# MySensors_org-BaseSensorWithPIR.net
KiCad netlist of a schematic drawn in EAGLE
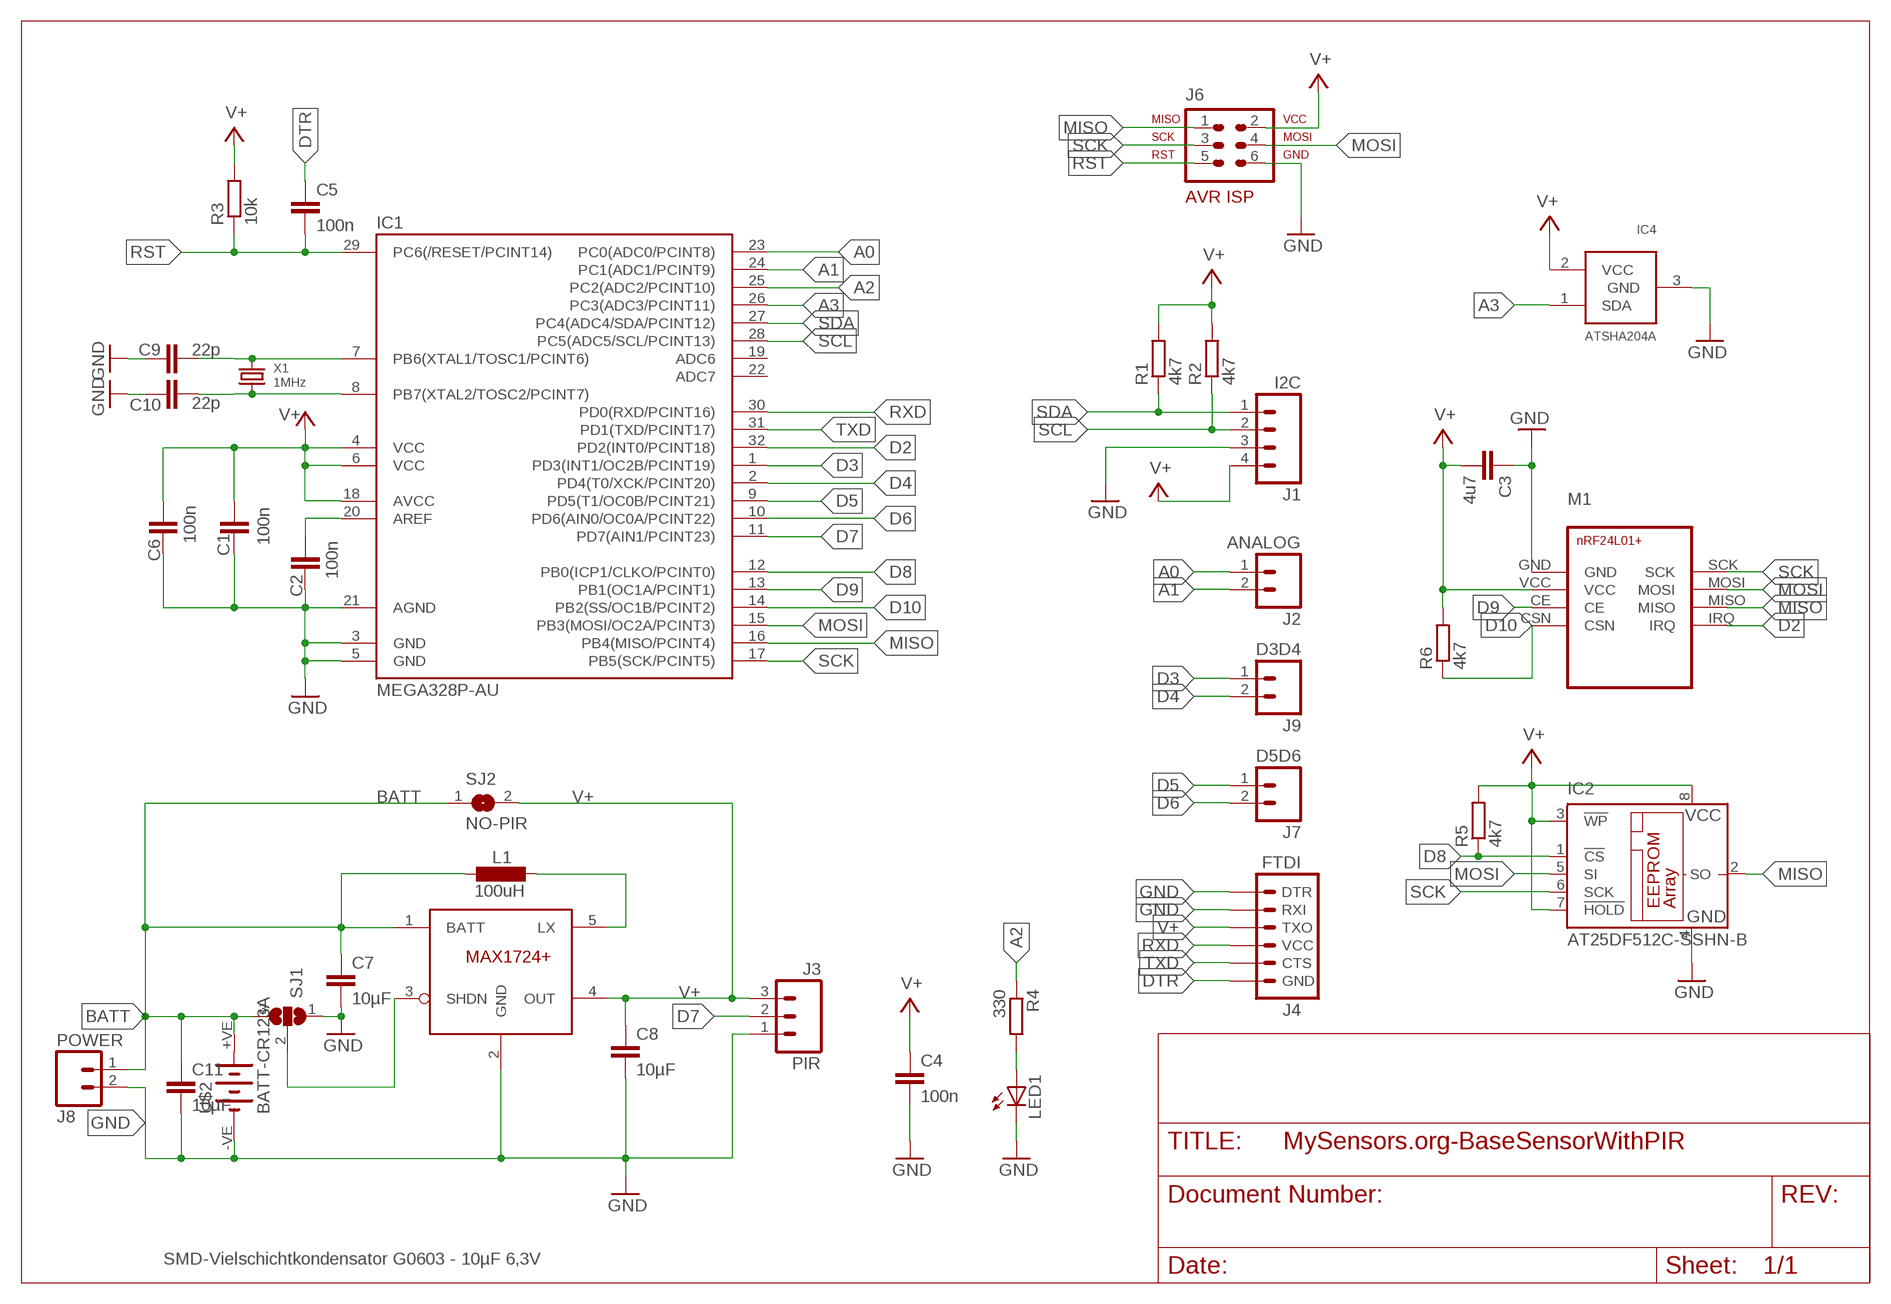
[diagram p0: schematic, sheet 1]

(export (version "E")
  (design (tool "Eeschema 10.0.6"))
  (components
    (comp (ref "C1")
      (value "100n")
      (footprint "eagle-import:C0603")
      (libsource (lib "eagle-import") (part "C-EUC0603"))
    )
    (comp (ref "C2")
      (value "100n")
      (footprint "eagle-import:C0603")
      (libsource (lib "eagle-import") (part "C-EUC0603"))
    )
    (comp (ref "C3")
      (value "4u7")
      (footprint "eagle-import:C0603")
      (libsource (lib "eagle-import") (part "C-EUC0603"))
    )
    (comp (ref "C4")
      (value "100n")
      (footprint "eagle-import:C0603")
      (libsource (lib "eagle-import") (part "C-EUC0603"))
    )
    (comp (ref "C5")
      (value "100n")
      (footprint "eagle-import:C0603")
      (libsource (lib "eagle-import") (part "C-EUC0603"))
    )
    (comp (ref "C6")
      (value "100n")
      (footprint "eagle-import:C0603")
      (libsource (lib "eagle-import") (part "C-EUC0603"))
    )
    (comp (ref "C7")
      (value "10µF")
      (footprint "eagle-import:C0603")
      (libsource (lib "eagle-import") (part "C-EUC0603"))
    )
    (comp (ref "C8")
      (value "10µF")
      (footprint "eagle-import:C0603")
      (libsource (lib "eagle-import") (part "C-EUC0603"))
    )
    (comp (ref "C9")
      (value "22p")
      (footprint "eagle-import:C0603")
      (libsource (lib "eagle-import") (part "C-EUC0603"))
    )
    (comp (ref "C10")
      (value "22p")
      (footprint "eagle-import:C0603")
      (libsource (lib "eagle-import") (part "C-EUC0603"))
    )
    (comp (ref "C11")
      (value "10µF")
      (footprint "eagle-import:C0603")
      (libsource (lib "eagle-import") (part "C-EUC0603"))
    )
    (comp (ref "IC1")
      (value "MEGA328P-AU")
      (footprint "eagle-import:TQFP32-08")
      (libsource (lib "eagle-import") (part "MEGA48/88/168-AU"))
    )
    (comp (ref "IC2")
      (value "AT25DF512C-SSHN-B")
      (footprint "eagle-import:SO-08")
      (fields (field (name "MF") "MICROCHIP") (field (name "MPN") "25AA080/SN"))
      (libsource (lib "eagle-import") (part "25SNAA080"))
    )
    (comp (ref "IC4")
      (value "ATSHA204A")
      (footprint "eagle-import:SOT23")
      (libsource (lib "eagle-import") (part "ATSHA204A"))
    )
    (comp (ref "J1")
      (value "I2C")
      (footprint "eagle-import:1X04_LOCK")
      (libsource (lib "eagle-import") (part "M04LOCK"))
    )
    (comp (ref "J2")
      (value "ANALOG")
      (footprint "eagle-import:1X02")
      (libsource (lib "eagle-import") (part "M02PTH"))
    )
    (comp (ref "J3")
      (value "PIR")
      (footprint "eagle-import:1X03_LOCK")
      (libsource (lib "eagle-import") (part "M03LOCK"))
    )
    (comp (ref "J4")
      (value "FTDI")
      (footprint "eagle-import:1X06_LOCK")
      (libsource (lib "eagle-import") (part "ARDUINO_SERIAL_PROGRAMLOCK"))
    )
    (comp (ref "J6")
      (value "N/M")
      (footprint "eagle-import:AVR-ISP-6")
      (libsource (lib "eagle-import") (part "AVR-ISP-6VERT"))
    )
    (comp (ref "J7")
      (value "D5D6")
      (footprint "eagle-import:1X02")
      (libsource (lib "eagle-import") (part "M02PTH"))
    )
    (comp (ref "J8")
      (value "POWER")
      (footprint "eagle-import:1X02")
      (libsource (lib "eagle-import") (part "M02PTH"))
    )
    (comp (ref "J9")
      (value "D3D4")
      (footprint "eagle-import:1X02")
      (libsource (lib "eagle-import") (part "M02PTH"))
    )
    (comp (ref "L1")
      (value "100uH")
      (footprint "eagle-import:1212FPS")
      (libsource (lib "eagle-import") (part "L-EU1212FPS"))
    )
    (comp (ref "LED1")
      (value "LEDSML0603")
      (footprint "eagle-import:SML0603")
      (libsource (lib "eagle-import") (part "LEDSML0603"))
    )
    (comp (ref "M1")
      (value "NRF24L01+NRF24L01+MINI")
      (footprint "eagle-import:NRF24L01+MINI")
      (libsource (lib "eagle-import") (part "NRF24L01+NRF24L01+MINI"))
    )
    (comp (ref "R1")
      (value "4k7")
      (footprint "eagle-import:R0603")
      (libsource (lib "eagle-import") (part "R-EU_R0603"))
    )
    (comp (ref "R2")
      (value "4k7")
      (footprint "eagle-import:R0603")
      (libsource (lib "eagle-import") (part "R-EU_R0603"))
    )
    (comp (ref "R3")
      (value "10k")
      (footprint "eagle-import:R0603")
      (libsource (lib "eagle-import") (part "R-EU_R0603"))
    )
    (comp (ref "R4")
      (value "330")
      (footprint "eagle-import:R0603")
      (libsource (lib "eagle-import") (part "R-EU_R0603"))
    )
    (comp (ref "R5")
      (value "4k7")
      (footprint "eagle-import:R0603")
      (libsource (lib "eagle-import") (part "R-EU_R0603"))
    )
    (comp (ref "R6")
      (value "4k7")
      (footprint "eagle-import:R0603")
      (libsource (lib "eagle-import") (part "R-EU_R0603"))
    )
    (comp (ref "SJ1")
      (value "SJ2W")
      (footprint "eagle-import:SJ_2")
      (libsource (lib "eagle-import") (part "SJ2W"))
    )
    (comp (ref "SJ2")
      (value "NO-PIR")
      (footprint "eagle-import:SJ")
      (libsource (lib "eagle-import") (part "SJ"))
    )
    (comp (ref "STEPUP")
      (value "MAX1724")
      (footprint "eagle-import:SOT23-5L")
      (libsource (lib "eagle-import") (part "MAX1724"))
    )
    (comp (ref "U$2")
      (value "BATT-CR123A")
      (footprint "eagle-import:KEYSTONE-2_3A")
      (libsource (lib "eagle-import") (part "BATT-CR123A"))
    )
    (comp (ref "X1")
      (value "1MHz")
      (footprint "eagle-import:2P-L3.2XW1.5MM")
      (libsource (lib "eagle-import") (part "CRYSTAL-306010055"))
    )
  )
  (nets
    (net (code "1") (name "A0") (class "Default")
      (node (ref "IC1") (pin "23") (pinfunction "PC0(ADC0/PCINT8)_23") (pintype "bidirectional"))
      (node (ref "J2") (pin "1") (pinfunction "1_1") (pintype "passive"))
    )
    (net (code "2") (name "A1") (class "Default")
      (node (ref "IC1") (pin "24") (pinfunction "PC1(ADC1/PCINT9)_24") (pintype "bidirectional"))
      (node (ref "J2") (pin "2") (pinfunction "2_2") (pintype "passive"))
    )
    (net (code "3") (name "A2") (class "Default")
      (node (ref "IC1") (pin "25") (pinfunction "PC2(ADC2/PCINT10)_25") (pintype "bidirectional"))
      (node (ref "R4") (pin "1") (pinfunction "1_1") (pintype "passive"))
    )
    (net (code "4") (name "A3") (class "Default")
      (node (ref "IC1") (pin "26") (pinfunction "PC3(ADC3/PCINT11)_26") (pintype "bidirectional"))
      (node (ref "IC4") (pin "1") (pinfunction "SDA_1") (pintype "bidirectional"))
    )
    (net (code "5") (name "BATT") (class "Default")
      (node (ref "C11") (pin "1") (pinfunction "1_1") (pintype "passive"))
      (node (ref "C7") (pin "1") (pinfunction "1_1") (pintype "passive"))
      (node (ref "J8") (pin "1") (pinfunction "1_1") (pintype "passive"))
      (node (ref "L1") (pin "1") (pinfunction "1_1") (pintype "passive"))
      (node (ref "SJ1") (pin "3") (pinfunction "3_3") (pintype "passive"))
      (node (ref "SJ2") (pin "1") (pinfunction "1_1") (pintype "passive"))
      (node (ref "STEPUP") (pin "1") (pinfunction "BATT_1") (pintype "power_in"))
      (node (ref "U$2") (pin "+VE") (pinfunction "+_+VE") (pintype "passive"))
    )
    (net (code "6") (name "D2") (class "Default")
      (node (ref "IC1") (pin "32") (pinfunction "PD2(INT0/PCINT18)_32") (pintype "bidirectional"))
      (node (ref "M1") (pin "IRQ") (pinfunction "IRQ_IRQ") (pintype "bidirectional"))
    )
    (net (code "7") (name "D3") (class "Default")
      (node (ref "IC1") (pin "1") (pinfunction "PD3(INT1/OC2B/PCINT19)_1") (pintype "bidirectional"))
      (node (ref "J9") (pin "1") (pinfunction "1_1") (pintype "passive"))
    )
    (net (code "8") (name "D4") (class "Default")
      (node (ref "IC1") (pin "2") (pinfunction "PD4(T0/XCK/PCINT20)_2") (pintype "bidirectional"))
      (node (ref "J9") (pin "2") (pinfunction "2_2") (pintype "passive"))
    )
    (net (code "9") (name "D5") (class "Default")
      (node (ref "IC1") (pin "9") (pinfunction "PD5(T1/OC0B/PCINT21)_9") (pintype "bidirectional"))
      (node (ref "J7") (pin "1") (pinfunction "1_1") (pintype "passive"))
    )
    (net (code "10") (name "D6") (class "Default")
      (node (ref "IC1") (pin "10") (pinfunction "PD6(AIN0/OC0A/PCINT22)_10") (pintype "bidirectional"))
      (node (ref "J7") (pin "2") (pinfunction "2_2") (pintype "passive"))
    )
    (net (code "11") (name "D7") (class "Default")
      (node (ref "IC1") (pin "11") (pinfunction "PD7(AIN1/PCINT23)_11") (pintype "bidirectional"))
      (node (ref "J3") (pin "2") (pinfunction "2_2") (pintype "passive"))
    )
    (net (code "12") (name "D8") (class "Default")
      (node (ref "IC1") (pin "12") (pinfunction "PB0(ICP1/CLKO/PCINT0)_12") (pintype "bidirectional"))
      (node (ref "IC2") (pin "1") (pinfunction "~{CS}_1") (pintype "input"))
      (node (ref "R5") (pin "1") (pinfunction "1_1") (pintype "passive"))
    )
    (net (code "13") (name "D9") (class "Default")
      (node (ref "IC1") (pin "13") (pinfunction "PB1(OC1A/PCINT1)_13") (pintype "bidirectional"))
      (node (ref "M1") (pin "CE") (pinfunction "CE_CE") (pintype "bidirectional"))
    )
    (net (code "14") (name "D10") (class "Default")
      (node (ref "IC1") (pin "14") (pinfunction "PB2(SS/OC1B/PCINT2)_14") (pintype "bidirectional"))
      (node (ref "M1") (pin "CSN") (pinfunction "CSN_CSN") (pintype "bidirectional"))
      (node (ref "R6") (pin "1") (pinfunction "1_1") (pintype "passive"))
    )
    (net (code "15") (name "DTR") (class "Default")
      (node (ref "C5") (pin "1") (pinfunction "1_1") (pintype "passive"))
      (node (ref "J4") (pin "6") (pinfunction "GND_6") (pintype "passive"))
    )
    (net (code "16") (name "GND") (class "Default")
      (node (ref "C1") (pin "2") (pinfunction "2_2") (pintype "passive"))
      (node (ref "C10") (pin "2") (pinfunction "2_2") (pintype "passive"))
      (node (ref "C11") (pin "2") (pinfunction "2_2") (pintype "passive"))
      (node (ref "C2") (pin "2") (pinfunction "2_2") (pintype "passive"))
      (node (ref "C3") (pin "1") (pinfunction "1_1") (pintype "passive"))
      (node (ref "C4") (pin "2") (pinfunction "2_2") (pintype "passive"))
      (node (ref "C6") (pin "2") (pinfunction "2_2") (pintype "passive"))
      (node (ref "C7") (pin "2") (pinfunction "2_2") (pintype "passive"))
      (node (ref "C8") (pin "2") (pinfunction "2_2") (pintype "passive"))
      (node (ref "C9") (pin "2") (pinfunction "2_2") (pintype "passive"))
      (node (ref "IC1") (pin "21") (pinfunction "AGND_21") (pintype "power_in"))
      (node (ref "IC1") (pin "3") (pinfunction "GND_3") (pintype "power_in"))
      (node (ref "IC1") (pin "5") (pinfunction "GND_5") (pintype "power_in"))
      (node (ref "IC2") (pin "4") (pinfunction "GND_4") (pintype "power_in"))
      (node (ref "IC4") (pin "3") (pinfunction "GND_3") (pintype "bidirectional"))
      (node (ref "J1") (pin "3") (pinfunction "3_3") (pintype "passive"))
      (node (ref "J3") (pin "1") (pinfunction "1_1") (pintype "passive"))
      (node (ref "J4") (pin "1") (pinfunction "DTR_1") (pintype "passive"))
      (node (ref "J4") (pin "2") (pinfunction "RXI_2") (pintype "passive"))
      (node (ref "J6") (pin "6") (pinfunction "6_6") (pintype "passive"))
      (node (ref "J8") (pin "2") (pinfunction "2_2") (pintype "passive"))
      (node (ref "LED1") (pin "C") (pinfunction "C_C") (pintype "passive"))
      (node (ref "M1") (pin "GND") (pinfunction "GND_GND") (pintype "power_in"))
      (node (ref "SJ1") (pin "1") (pinfunction "1_1") (pintype "passive"))
      (node (ref "STEPUP") (pin "2") (pinfunction "GND_2") (pintype "power_in"))
      (node (ref "U$2") (pin "-VE") (pinfunction "-_-VE") (pintype "passive"))
    )
    (net (code "17") (name "MISO") (class "Default")
      (node (ref "IC1") (pin "16") (pinfunction "PB4(MISO/PCINT4)_16") (pintype "bidirectional"))
      (node (ref "IC2") (pin "2") (pinfunction "SO_2") (pintype "bidirectional"))
      (node (ref "J6") (pin "1") (pinfunction "1_1") (pintype "passive"))
      (node (ref "M1") (pin "MISO") (pinfunction "MISO_MISO") (pintype "bidirectional"))
    )
    (net (code "18") (name "MOSI") (class "Default")
      (node (ref "IC1") (pin "15") (pinfunction "PB3(MOSI/OC2A/PCINT3)_15") (pintype "bidirectional"))
      (node (ref "IC2") (pin "5") (pinfunction "SI_5") (pintype "input"))
      (node (ref "J6") (pin "4") (pinfunction "4_4") (pintype "passive"))
      (node (ref "M1") (pin "MOSI") (pinfunction "MOSI_MOSI") (pintype "bidirectional"))
    )
    (net (code "19") (name "Net-(IC1-AREF)") (class "Default")
      (node (ref "C2") (pin "1") (pinfunction "1_1") (pintype "passive"))
      (node (ref "IC1") (pin "20") (pinfunction "AREF_20") (pintype "passive"))
    )
    (net (code "20") (name "Net-(IC1-PB6(XTAL1{slash}TOSC1{slash}PCINT6))") (class "Default")
      (node (ref "C9") (pin "1") (pinfunction "1_1") (pintype "passive"))
      (node (ref "IC1") (pin "7") (pinfunction "PB6(XTAL1/TOSC1/PCINT6)_7") (pintype "bidirectional"))
      (node (ref "X1") (pin "2") (pinfunction "2_2") (pintype "passive"))
    )
    (net (code "21") (name "Net-(IC1-PB7(XTAL2{slash}TOSC2{slash}PCINT7))") (class "Default")
      (node (ref "C10") (pin "1") (pinfunction "1_1") (pintype "passive"))
      (node (ref "IC1") (pin "8") (pinfunction "PB7(XTAL2/TOSC2/PCINT7)_8") (pintype "bidirectional"))
      (node (ref "X1") (pin "1") (pinfunction "1_1") (pintype "passive"))
    )
    (net (code "22") (name "Net-(LED1-PadA)") (class "Default")
      (node (ref "LED1") (pin "A") (pinfunction "A_A") (pintype "passive"))
      (node (ref "R4") (pin "2") (pinfunction "2_2") (pintype "passive"))
    )
    (net (code "23") (name "Net-(STEPUP-LX)") (class "Default")
      (node (ref "L1") (pin "2") (pinfunction "2_2") (pintype "passive"))
      (node (ref "STEPUP") (pin "5") (pinfunction "LX_5") (pintype "input"))
    )
    (net (code "24") (name "Net-(STEPUP-SHDN)") (class "Default")
      (node (ref "SJ1") (pin "2") (pinfunction "2_2") (pintype "passive"))
      (node (ref "STEPUP") (pin "3") (pinfunction "SHDN_3") (pintype "bidirectional"))
    )
    (net (code "25") (name "RST") (class "Default")
      (node (ref "C5") (pin "2") (pinfunction "2_2") (pintype "passive"))
      (node (ref "IC1") (pin "29") (pinfunction "PC6(/RESET/PCINT14)_29") (pintype "bidirectional"))
      (node (ref "J6") (pin "5") (pinfunction "5_5") (pintype "passive"))
      (node (ref "R3") (pin "1") (pinfunction "1_1") (pintype "passive"))
    )
    (net (code "26") (name "RXD") (class "Default")
      (node (ref "IC1") (pin "30") (pinfunction "PD0(RXD/PCINT16)_30") (pintype "bidirectional"))
      (node (ref "J4") (pin "4") (pinfunction "VCC_4") (pintype "passive"))
    )
    (net (code "27") (name "SCK") (class "Default")
      (node (ref "IC1") (pin "17") (pinfunction "PB5(SCK/PCINT5)_17") (pintype "bidirectional"))
      (node (ref "IC2") (pin "6") (pinfunction "SCK_6") (pintype "input"))
      (node (ref "J6") (pin "3") (pinfunction "3_3") (pintype "passive"))
      (node (ref "M1") (pin "SCK") (pinfunction "SCK_SCK") (pintype "bidirectional"))
    )
    (net (code "28") (name "SCL") (class "Default")
      (node (ref "IC1") (pin "28") (pinfunction "PC5(ADC5/SCL/PCINT13)_28") (pintype "bidirectional"))
      (node (ref "J1") (pin "2") (pinfunction "2_2") (pintype "passive"))
      (node (ref "R2") (pin "1") (pinfunction "1_1") (pintype "passive"))
    )
    (net (code "29") (name "SDA") (class "Default")
      (node (ref "IC1") (pin "27") (pinfunction "PC4(ADC4/SDA/PCINT12)_27") (pintype "bidirectional"))
      (node (ref "J1") (pin "1") (pinfunction "1_1") (pintype "passive"))
      (node (ref "R1") (pin "1") (pinfunction "1_1") (pintype "passive"))
    )
    (net (code "30") (name "TXD") (class "Default")
      (node (ref "IC1") (pin "31") (pinfunction "PD1(TXD/PCINT17)_31") (pintype "bidirectional"))
      (node (ref "J4") (pin "5") (pinfunction "CTS_5") (pintype "passive"))
    )
    (net (code "31") (name "V+") (class "Default")
      (node (ref "C1") (pin "1") (pinfunction "1_1") (pintype "passive"))
      (node (ref "C3") (pin "2") (pinfunction "2_2") (pintype "passive"))
      (node (ref "C4") (pin "1") (pinfunction "1_1") (pintype "passive"))
      (node (ref "C6") (pin "1") (pinfunction "1_1") (pintype "passive"))
      (node (ref "C8") (pin "1") (pinfunction "1_1") (pintype "passive"))
      (node (ref "IC1") (pin "18") (pinfunction "AVCC_18") (pintype "passive"))
      (node (ref "IC1") (pin "4") (pinfunction "VCC_4") (pintype "power_in"))
      (node (ref "IC1") (pin "6") (pinfunction "VCC_6") (pintype "power_in"))
      (node (ref "IC2") (pin "3") (pinfunction "~{WP}_3") (pintype "input"))
      (node (ref "IC2") (pin "7") (pinfunction "~{HOLD}_7") (pintype "input"))
      (node (ref "IC2") (pin "8") (pinfunction "VCC_8") (pintype "power_in"))
      (node (ref "IC4") (pin "2") (pinfunction "VCC_2") (pintype "bidirectional"))
      (node (ref "J1") (pin "4") (pinfunction "4_4") (pintype "passive"))
      (node (ref "J3") (pin "3") (pinfunction "3_3") (pintype "passive"))
      (node (ref "J4") (pin "3") (pinfunction "TXO_3") (pintype "passive"))
      (node (ref "J6") (pin "2") (pinfunction "2_2") (pintype "passive"))
      (node (ref "M1") (pin "VCC") (pinfunction "VCC_VCC") (pintype "power_in"))
      (node (ref "R1") (pin "2") (pinfunction "2_2") (pintype "passive"))
      (node (ref "R2") (pin "2") (pinfunction "2_2") (pintype "passive"))
      (node (ref "R3") (pin "2") (pinfunction "2_2") (pintype "passive"))
      (node (ref "R5") (pin "2") (pinfunction "2_2") (pintype "passive"))
      (node (ref "R6") (pin "2") (pinfunction "2_2") (pintype "passive"))
      (node (ref "SJ2") (pin "2") (pinfunction "2_2") (pintype "passive"))
      (node (ref "STEPUP") (pin "4") (pinfunction "OUT_4") (pintype "output"))
    )
    (net (code "32") (name "unconnected-(IC1-ADC6-Pad19)") (class "Default")
      (node (ref "IC1") (pin "19") (pinfunction "ADC6_19") (pintype "passive"))
    )
    (net (code "33") (name "unconnected-(IC1-ADC7-Pad22)") (class "Default")
      (node (ref "IC1") (pin "22") (pinfunction "ADC7_22") (pintype "passive"))
    )
  )
)
